# ProProject_AGV_VH723_MAIN_BOARD_2024-06-.net
KiCad netlist of a schematic drawn in EasyEDA Pro
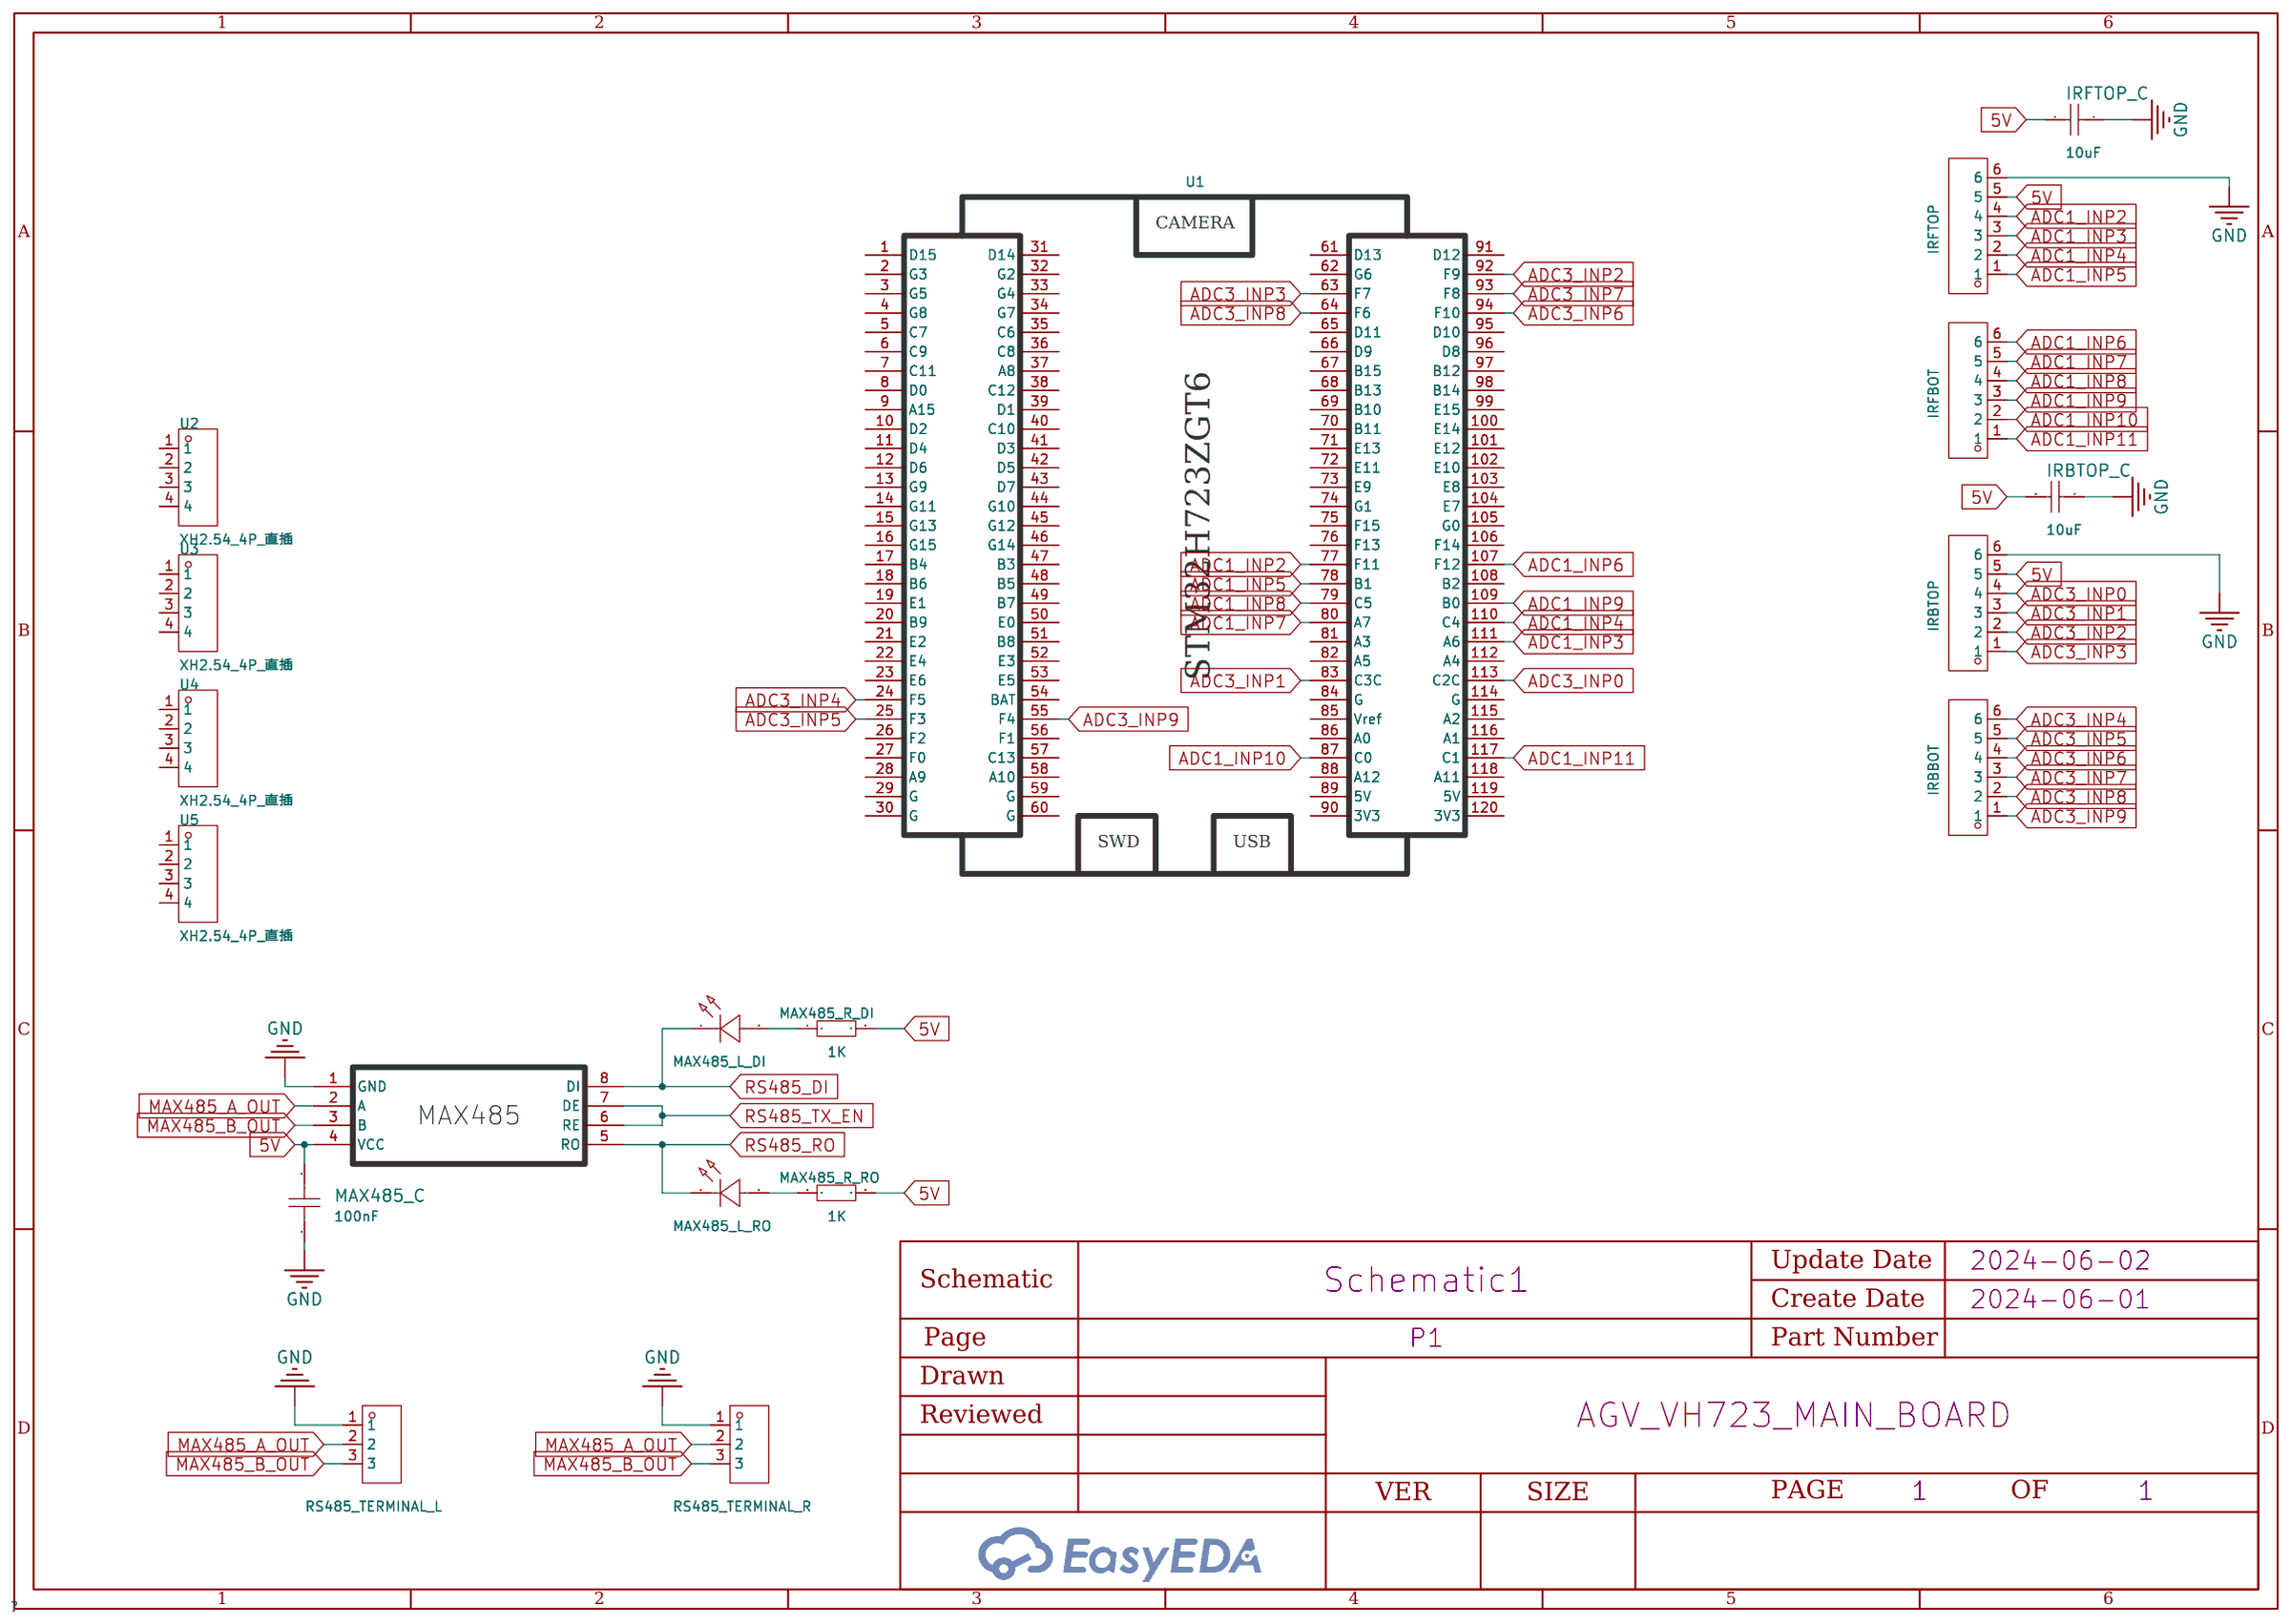
[diagram p0: schematic sheet]

(export (version "E")
  (design (tool "Eeschema 10.0.6"))
  (components
    (comp (ref "IRBBOT")
      (value "XH2.54*6P_直插")
      (footprint "easyedapro:CONN-TH_XH2.54-6P")
      (libsource (lib "easyedapro") (part "XH2.54*6P_直插"))
    )
    (comp (ref "IRBTOP")
      (value "XH2.54*6P_直插")
      (footprint "easyedapro:CONN-TH_XH2.54-6P")
      (libsource (lib "easyedapro") (part "XH2.54*6P_直插"))
    )
    (comp (ref "IRBTOP_C")
      (value "10uF")
      (footprint "easyedapro:C1206")
      (fields
        (field (name "Manufacturer Part") "CL31A106KOHNNNE")
        (field (name "Manufacturer") "SAMSUNG(三星)")
      )
      (libsource (lib "easyedapro") (part "CL31A106KOHNNNE"))
    )
    (comp (ref "IRFBOT")
      (value "XH2.54*6P_直插")
      (footprint "easyedapro:CONN-TH_XH2.54-6P")
      (libsource (lib "easyedapro") (part "XH2.54*6P_直插"))
    )
    (comp (ref "IRFTOP")
      (value "XH2.54*6P_直插")
      (footprint "easyedapro:CONN-TH_XH2.54-6P")
      (libsource (lib "easyedapro") (part "XH2.54*6P_直插"))
    )
    (comp (ref "IRFTOP_C")
      (value "10uF")
      (footprint "easyedapro:C1206")
      (fields
        (field (name "Manufacturer Part") "CL31A106KOHNNNE")
        (field (name "Manufacturer") "SAMSUNG(三星)")
      )
      (libsource (lib "easyedapro") (part "CL31A106KOHNNNE"))
    )
    (comp (ref "MAX485_C")
      (value "100nF")
      (footprint "easyedapro:C1206")
      (fields (field (name "Manufacturer Part") "1206B104K500CT") (field (name "Manufacturer") "Walsin(华新科)"))
      (libsource (lib "easyedapro") (part "1206B104K500"))
    )
    (comp (ref "MAX485_L_DI")
      (value "LED1206")
      (footprint "easyedapro:LED1206-RD")
      (libsource (lib "easyedapro") (part "LED1206"))
    )
    (comp (ref "MAX485_L_RO")
      (value "LED1206")
      (footprint "easyedapro:LED1206-RD")
      (libsource (lib "easyedapro") (part "LED1206"))
    )
    (comp (ref "MAX485_R_DI")
      (value "1K")
      (footprint "easyedapro:R0603")
      (libsource (lib "easyedapro") (part "Res"))
    )
    (comp (ref "MAX485_R_RO")
      (value "1K")
      (footprint "easyedapro:R0603")
      (libsource (lib "easyedapro") (part "Res"))
    )
    (comp (ref "RS485_TERMINAL_L")
      (value "MX128L-5.08-03P-GN01-Cu-Y-A")
      (footprint "easyedapro:CONN-TH_3P-P5.08_MX128L-5.08-03P-GN01-CU-Y-A")
      (fields (field (name "Manufacturer") "MAX(迈旭)"))
      (libsource (lib "easyedapro") (part "MX128L-5.08-03P-GN01-CU-Y-A"))
    )
    (comp (ref "RS485_TERMINAL_R")
      (value "MX128L-5.08-03P-GN01-Cu-Y-A")
      (footprint "easyedapro:CONN-TH_3P-P5.08_MX128L-5.08-03P-GN01-CU-Y-A")
      (fields (field (name "Manufacturer") "MAX(迈旭)"))
      (libsource (lib "easyedapro") (part "MX128L-5.08-03P-GN01-CU-Y-A"))
    )
    (comp (ref "U1")
      (value "STM32H723ZGT6")
      (footprint "easyedapro:STM32H723ZGT6 DEV BOARD FOOTPRINT")
      (description "STM32H723ZGT6 Core Board and Development Board model made by Araf Israk")
      (libsource (lib "easyedapro") (part "stm32h723zgt6 dev board"))
    )
    (comp (ref "U2")
      (value "XH2.54_4P_直插")
      (footprint "easyedapro:CONN-TH_4P-P2.50-XH2.54-4P")
      (libsource (lib "easyedapro") (part "XH2.54_4P_直插"))
    )
    (comp (ref "U3")
      (value "XH2.54_4P_直插")
      (footprint "easyedapro:CONN-TH_4P-P2.50-XH2.54-4P")
      (libsource (lib "easyedapro") (part "XH2.54_4P_直插"))
    )
    (comp (ref "U4")
      (value "XH2.54_4P_直插")
      (footprint "easyedapro:CONN-TH_4P-P2.50-XH2.54-4P")
      (libsource (lib "easyedapro") (part "XH2.54_4P_直插"))
    )
    (comp (ref "U5")
      (value "XH2.54_4P_直插")
      (footprint "easyedapro:CONN-TH_4P-P2.50-XH2.54-4P")
      (libsource (lib "easyedapro") (part "XH2.54_4P_直插"))
    )
    (comp (ref "U6")
      (value "MAX485 IC RS485 Module")
      (footprint "easyedapro:RS485-arafisrak")
      (description "MAX485 IC RS485 Module (modified)")
      (libsource (lib "easyedapro") (part "RS485 Module"))
    )
  )
  (nets
    (net (code "1") (name "5V") (class "Default")
      (node (ref "IRBTOP") (pin "5") (pinfunction "5_5") (pintype "unspecified"))
      (node (ref "IRBTOP_C") (pin "2") (pinfunction "2_2") (pintype "input"))
      (node (ref "IRFTOP") (pin "5") (pinfunction "5_5") (pintype "unspecified"))
      (node (ref "IRFTOP_C") (pin "2") (pinfunction "2_2") (pintype "input"))
      (node (ref "MAX485_C") (pin "2") (pinfunction "2_2") (pintype "input"))
      (node (ref "MAX485_R_DI") (pin "2") (pinfunction "2_2") (pintype "input"))
      (node (ref "MAX485_R_RO") (pin "2") (pinfunction "2_2") (pintype "input"))
      (node (ref "U6") (pin "4") (pinfunction "VCC_4") (pintype "input"))
    )
    (net (code "2") (name "ADC1_INP2") (class "Default")
      (node (ref "IRFTOP") (pin "4") (pinfunction "4_4") (pintype "unspecified"))
      (node (ref "U1") (pin "77") (pinfunction "F11_77") (pintype "input"))
    )
    (net (code "3") (name "ADC1_INP3") (class "Default")
      (node (ref "IRFTOP") (pin "3") (pinfunction "3_3") (pintype "unspecified"))
      (node (ref "U1") (pin "111") (pinfunction "A6_111") (pintype "input"))
    )
    (net (code "4") (name "ADC1_INP4") (class "Default")
      (node (ref "IRFTOP") (pin "2") (pinfunction "2_2") (pintype "unspecified"))
      (node (ref "U1") (pin "110") (pinfunction "C4_110") (pintype "input"))
    )
    (net (code "5") (name "ADC1_INP5") (class "Default")
      (node (ref "IRFTOP") (pin "1") (pinfunction "1_1") (pintype "unspecified"))
      (node (ref "U1") (pin "78") (pinfunction "B1_78") (pintype "input"))
    )
    (net (code "6") (name "ADC1_INP6") (class "Default")
      (node (ref "IRFBOT") (pin "6") (pinfunction "6_6") (pintype "unspecified"))
      (node (ref "U1") (pin "107") (pinfunction "F12_107") (pintype "input"))
    )
    (net (code "7") (name "ADC1_INP7") (class "Default")
      (node (ref "IRFBOT") (pin "5") (pinfunction "5_5") (pintype "unspecified"))
      (node (ref "U1") (pin "80") (pinfunction "A7_80") (pintype "input"))
    )
    (net (code "8") (name "ADC1_INP8") (class "Default")
      (node (ref "IRFBOT") (pin "4") (pinfunction "4_4") (pintype "unspecified"))
      (node (ref "U1") (pin "79") (pinfunction "C5_79") (pintype "input"))
    )
    (net (code "9") (name "ADC1_INP9") (class "Default")
      (node (ref "IRFBOT") (pin "3") (pinfunction "3_3") (pintype "unspecified"))
      (node (ref "U1") (pin "109") (pinfunction "B0_109") (pintype "input"))
    )
    (net (code "10") (name "ADC1_INP10") (class "Default")
      (node (ref "IRFBOT") (pin "2") (pinfunction "2_2") (pintype "unspecified"))
      (node (ref "U1") (pin "87") (pinfunction "C0_87") (pintype "input"))
    )
    (net (code "11") (name "ADC1_INP11") (class "Default")
      (node (ref "IRFBOT") (pin "1") (pinfunction "1_1") (pintype "unspecified"))
      (node (ref "U1") (pin "117") (pinfunction "C1_117") (pintype "input"))
    )
    (net (code "12") (name "ADC3_INP0") (class "Default")
      (node (ref "IRBTOP") (pin "4") (pinfunction "4_4") (pintype "unspecified"))
      (node (ref "U1") (pin "113") (pinfunction "C2C_113") (pintype "input"))
    )
    (net (code "13") (name "ADC3_INP1") (class "Default")
      (node (ref "IRBTOP") (pin "3") (pinfunction "3_3") (pintype "unspecified"))
      (node (ref "U1") (pin "83") (pinfunction "C3C_83") (pintype "input"))
    )
    (net (code "14") (name "ADC3_INP2") (class "Default")
      (node (ref "IRBTOP") (pin "2") (pinfunction "2_2") (pintype "unspecified"))
      (node (ref "U1") (pin "92") (pinfunction "F9_92") (pintype "input"))
    )
    (net (code "15") (name "ADC3_INP3") (class "Default")
      (node (ref "IRBTOP") (pin "1") (pinfunction "1_1") (pintype "unspecified"))
      (node (ref "U1") (pin "63") (pinfunction "F7_63") (pintype "input"))
    )
    (net (code "16") (name "ADC3_INP4") (class "Default")
      (node (ref "IRBBOT") (pin "6") (pinfunction "6_6") (pintype "unspecified"))
      (node (ref "U1") (pin "24") (pinfunction "F5_24") (pintype "input"))
    )
    (net (code "17") (name "ADC3_INP5") (class "Default")
      (node (ref "IRBBOT") (pin "5") (pinfunction "5_5") (pintype "unspecified"))
      (node (ref "U1") (pin "25") (pinfunction "F3_25") (pintype "input"))
    )
    (net (code "18") (name "ADC3_INP6") (class "Default")
      (node (ref "IRBBOT") (pin "4") (pinfunction "4_4") (pintype "unspecified"))
      (node (ref "U1") (pin "94") (pinfunction "F10_94") (pintype "input"))
    )
    (net (code "19") (name "ADC3_INP7") (class "Default")
      (node (ref "IRBBOT") (pin "3") (pinfunction "3_3") (pintype "unspecified"))
      (node (ref "U1") (pin "93") (pinfunction "F8_93") (pintype "input"))
    )
    (net (code "20") (name "ADC3_INP8") (class "Default")
      (node (ref "IRBBOT") (pin "2") (pinfunction "2_2") (pintype "unspecified"))
      (node (ref "U1") (pin "64") (pinfunction "F6_64") (pintype "input"))
    )
    (net (code "21") (name "ADC3_INP9") (class "Default")
      (node (ref "IRBBOT") (pin "1") (pinfunction "1_1") (pintype "unspecified"))
      (node (ref "U1") (pin "55") (pinfunction "F4_55") (pintype "input"))
    )
    (net (code "22") (name "GND") (class "Default")
      (node (ref "IRBTOP") (pin "6") (pinfunction "6_6") (pintype "unspecified"))
      (node (ref "IRBTOP_C") (pin "1") (pinfunction "1_1") (pintype "input"))
      (node (ref "IRFTOP") (pin "6") (pinfunction "6_6") (pintype "unspecified"))
      (node (ref "IRFTOP_C") (pin "1") (pinfunction "1_1") (pintype "input"))
      (node (ref "MAX485_C") (pin "1") (pinfunction "1_1") (pintype "input"))
      (node (ref "RS485_TERMINAL_L") (pin "1") (pinfunction "1_1") (pintype "unspecified"))
      (node (ref "RS485_TERMINAL_R") (pin "1") (pinfunction "1_1") (pintype "unspecified"))
      (node (ref "U6") (pin "1") (pinfunction "GND_1") (pintype "input"))
    )
    (net (code "23") (name "MAX485_A_OUT") (class "Default")
      (node (ref "RS485_TERMINAL_L") (pin "2") (pinfunction "2_2") (pintype "unspecified"))
      (node (ref "RS485_TERMINAL_R") (pin "2") (pinfunction "2_2") (pintype "unspecified"))
      (node (ref "U6") (pin "2") (pinfunction "A_2") (pintype "input"))
    )
    (net (code "24") (name "MAX485_B_OUT") (class "Default")
      (node (ref "RS485_TERMINAL_L") (pin "3") (pinfunction "3_3") (pintype "unspecified"))
      (node (ref "RS485_TERMINAL_R") (pin "3") (pinfunction "3_3") (pintype "unspecified"))
      (node (ref "U6") (pin "3") (pinfunction "B_3") (pintype "input"))
    )
    (net (code "25") (name "Net-(MAX485_L_DI-A)") (class "Default")
      (node (ref "MAX485_L_DI") (pin "2") (pinfunction "A_2") (pintype "input"))
      (node (ref "MAX485_R_DI") (pin "1") (pinfunction "1_1") (pintype "input"))
    )
    (net (code "26") (name "Net-(MAX485_L_RO-A)") (class "Default")
      (node (ref "MAX485_L_RO") (pin "2") (pinfunction "A_2") (pintype "input"))
      (node (ref "MAX485_R_RO") (pin "1") (pinfunction "1_1") (pintype "input"))
    )
    (net (code "27") (name "RS485_DI") (class "Default")
      (node (ref "MAX485_L_DI") (pin "1") (pinfunction "K_1") (pintype "input"))
      (node (ref "U6") (pin "8") (pinfunction "DI_8") (pintype "input"))
    )
    (net (code "28") (name "RS485_RO") (class "Default")
      (node (ref "MAX485_L_RO") (pin "1") (pinfunction "K_1") (pintype "input"))
      (node (ref "U6") (pin "5") (pinfunction "RO_5") (pintype "input"))
    )
    (net (code "29") (name "RS485_TX_EN") (class "Default")
      (node (ref "U6") (pin "6") (pinfunction "RE_6") (pintype "input"))
      (node (ref "U6") (pin "7") (pinfunction "DE_7") (pintype "input"))
    )
    (net (code "30") (name "unconnected-(U1-3V3-Pad90)") (class "Default")
      (node (ref "U1") (pin "90") (pinfunction "3V3_90") (pintype "input"))
    )
    (net (code "31") (name "unconnected-(U1-3V3-Pad120)") (class "Default")
      (node (ref "U1") (pin "120") (pinfunction "3V3_120") (pintype "input"))
    )
    (net (code "32") (name "unconnected-(U1-5V-Pad89)") (class "Default")
      (node (ref "U1") (pin "89") (pinfunction "5V_89") (pintype "input"))
    )
    (net (code "33") (name "unconnected-(U1-5V-Pad119)") (class "Default")
      (node (ref "U1") (pin "119") (pinfunction "5V_119") (pintype "input"))
    )
    (net (code "34") (name "unconnected-(U1-A0-Pad86)") (class "Default")
      (node (ref "U1") (pin "86") (pinfunction "A0_86") (pintype "input"))
    )
    (net (code "35") (name "unconnected-(U1-A1-Pad116)") (class "Default")
      (node (ref "U1") (pin "116") (pinfunction "A1_116") (pintype "input"))
    )
    (net (code "36") (name "unconnected-(U1-A2-Pad115)") (class "Default")
      (node (ref "U1") (pin "115") (pinfunction "A2_115") (pintype "input"))
    )
    (net (code "37") (name "unconnected-(U1-A3-Pad81)") (class "Default")
      (node (ref "U1") (pin "81") (pinfunction "A3_81") (pintype "input"))
    )
    (net (code "38") (name "unconnected-(U1-A4-Pad112)") (class "Default")
      (node (ref "U1") (pin "112") (pinfunction "A4_112") (pintype "input"))
    )
    (net (code "39") (name "unconnected-(U1-A5-Pad82)") (class "Default")
      (node (ref "U1") (pin "82") (pinfunction "A5_82") (pintype "input"))
    )
    (net (code "40") (name "unconnected-(U1-A8-Pad37)") (class "Default")
      (node (ref "U1") (pin "37") (pinfunction "A8_37") (pintype "input"))
    )
    (net (code "41") (name "unconnected-(U1-A9-Pad28)") (class "Default")
      (node (ref "U1") (pin "28") (pinfunction "A9_28") (pintype "input"))
    )
    (net (code "42") (name "unconnected-(U1-A10-Pad58)") (class "Default")
      (node (ref "U1") (pin "58") (pinfunction "A10_58") (pintype "input"))
    )
    (net (code "43") (name "unconnected-(U1-A11-Pad118)") (class "Default")
      (node (ref "U1") (pin "118") (pinfunction "A11_118") (pintype "input"))
    )
    (net (code "44") (name "unconnected-(U1-A12-Pad88)") (class "Default")
      (node (ref "U1") (pin "88") (pinfunction "A12_88") (pintype "input"))
    )
    (net (code "45") (name "unconnected-(U1-A15-Pad9)") (class "Default")
      (node (ref "U1") (pin "9") (pinfunction "A15_9") (pintype "input"))
    )
    (net (code "46") (name "unconnected-(U1-B2-Pad108)") (class "Default")
      (node (ref "U1") (pin "108") (pinfunction "B2_108") (pintype "input"))
    )
    (net (code "47") (name "unconnected-(U1-B3-Pad47)") (class "Default")
      (node (ref "U1") (pin "47") (pinfunction "B3_47") (pintype "input"))
    )
    (net (code "48") (name "unconnected-(U1-B4-Pad17)") (class "Default")
      (node (ref "U1") (pin "17") (pinfunction "B4_17") (pintype "input"))
    )
    (net (code "49") (name "unconnected-(U1-B5-Pad48)") (class "Default")
      (node (ref "U1") (pin "48") (pinfunction "B5_48") (pintype "input"))
    )
    (net (code "50") (name "unconnected-(U1-B6-Pad18)") (class "Default")
      (node (ref "U1") (pin "18") (pinfunction "B6_18") (pintype "input"))
    )
    (net (code "51") (name "unconnected-(U1-B7-Pad49)") (class "Default")
      (node (ref "U1") (pin "49") (pinfunction "B7_49") (pintype "input"))
    )
    (net (code "52") (name "unconnected-(U1-B8-Pad51)") (class "Default")
      (node (ref "U1") (pin "51") (pinfunction "B8_51") (pintype "input"))
    )
    (net (code "53") (name "unconnected-(U1-B9-Pad20)") (class "Default")
      (node (ref "U1") (pin "20") (pinfunction "B9_20") (pintype "input"))
    )
    (net (code "54") (name "unconnected-(U1-B10-Pad69)") (class "Default")
      (node (ref "U1") (pin "69") (pinfunction "B10_69") (pintype "input"))
    )
    (net (code "55") (name "unconnected-(U1-B11-Pad70)") (class "Default")
      (node (ref "U1") (pin "70") (pinfunction "B11_70") (pintype "input"))
    )
    (net (code "56") (name "unconnected-(U1-B12-Pad97)") (class "Default")
      (node (ref "U1") (pin "97") (pinfunction "B12_97") (pintype "input"))
    )
    (net (code "57") (name "unconnected-(U1-B13-Pad68)") (class "Default")
      (node (ref "U1") (pin "68") (pinfunction "B13_68") (pintype "input"))
    )
    (net (code "58") (name "unconnected-(U1-B14-Pad98)") (class "Default")
      (node (ref "U1") (pin "98") (pinfunction "B14_98") (pintype "input"))
    )
    (net (code "59") (name "unconnected-(U1-B15-Pad67)") (class "Default")
      (node (ref "U1") (pin "67") (pinfunction "B15_67") (pintype "input"))
    )
    (net (code "60") (name "unconnected-(U1-BAT-Pad54)") (class "Default")
      (node (ref "U1") (pin "54") (pinfunction "BAT_54") (pintype "input"))
    )
    (net (code "61") (name "unconnected-(U1-C6-Pad35)") (class "Default")
      (node (ref "U1") (pin "35") (pinfunction "C6_35") (pintype "input"))
    )
    (net (code "62") (name "unconnected-(U1-C7-Pad5)") (class "Default")
      (node (ref "U1") (pin "5") (pinfunction "C7_5") (pintype "input"))
    )
    (net (code "63") (name "unconnected-(U1-C8-Pad36)") (class "Default")
      (node (ref "U1") (pin "36") (pinfunction "C8_36") (pintype "input"))
    )
    (net (code "64") (name "unconnected-(U1-C9-Pad6)") (class "Default")
      (node (ref "U1") (pin "6") (pinfunction "C9_6") (pintype "input"))
    )
    (net (code "65") (name "unconnected-(U1-C10-Pad40)") (class "Default")
      (node (ref "U1") (pin "40") (pinfunction "C10_40") (pintype "input"))
    )
    (net (code "66") (name "unconnected-(U1-C11-Pad7)") (class "Default")
      (node (ref "U1") (pin "7") (pinfunction "C11_7") (pintype "input"))
    )
    (net (code "67") (name "unconnected-(U1-C12-Pad38)") (class "Default")
      (node (ref "U1") (pin "38") (pinfunction "C12_38") (pintype "input"))
    )
    (net (code "68") (name "unconnected-(U1-C13-Pad57)") (class "Default")
      (node (ref "U1") (pin "57") (pinfunction "C13_57") (pintype "input"))
    )
    (net (code "69") (name "unconnected-(U1-D0-Pad8)") (class "Default")
      (node (ref "U1") (pin "8") (pinfunction "D0_8") (pintype "input"))
    )
    (net (code "70") (name "unconnected-(U1-D1-Pad39)") (class "Default")
      (node (ref "U1") (pin "39") (pinfunction "D1_39") (pintype "input"))
    )
    (net (code "71") (name "unconnected-(U1-D2-Pad10)") (class "Default")
      (node (ref "U1") (pin "10") (pinfunction "D2_10") (pintype "input"))
    )
    (net (code "72") (name "unconnected-(U1-D3-Pad41)") (class "Default")
      (node (ref "U1") (pin "41") (pinfunction "D3_41") (pintype "input"))
    )
    (net (code "73") (name "unconnected-(U1-D4-Pad11)") (class "Default")
      (node (ref "U1") (pin "11") (pinfunction "D4_11") (pintype "input"))
    )
    (net (code "74") (name "unconnected-(U1-D5-Pad42)") (class "Default")
      (node (ref "U1") (pin "42") (pinfunction "D5_42") (pintype "input"))
    )
    (net (code "75") (name "unconnected-(U1-D6-Pad12)") (class "Default")
      (node (ref "U1") (pin "12") (pinfunction "D6_12") (pintype "input"))
    )
    (net (code "76") (name "unconnected-(U1-D7-Pad43)") (class "Default")
      (node (ref "U1") (pin "43") (pinfunction "D7_43") (pintype "input"))
    )
    (net (code "77") (name "unconnected-(U1-D8-Pad96)") (class "Default")
      (node (ref "U1") (pin "96") (pinfunction "D8_96") (pintype "input"))
    )
    (net (code "78") (name "unconnected-(U1-D9-Pad66)") (class "Default")
      (node (ref "U1") (pin "66") (pinfunction "D9_66") (pintype "input"))
    )
    (net (code "79") (name "unconnected-(U1-D10-Pad95)") (class "Default")
      (node (ref "U1") (pin "95") (pinfunction "D10_95") (pintype "input"))
    )
    (net (code "80") (name "unconnected-(U1-D11-Pad65)") (class "Default")
      (node (ref "U1") (pin "65") (pinfunction "D11_65") (pintype "input"))
    )
    (net (code "81") (name "unconnected-(U1-D12-Pad91)") (class "Default")
      (node (ref "U1") (pin "91") (pinfunction "D12_91") (pintype "input"))
    )
    (net (code "82") (name "unconnected-(U1-D13-Pad61)") (class "Default")
      (node (ref "U1") (pin "61") (pinfunction "D13_61") (pintype "input"))
    )
    (net (code "83") (name "unconnected-(U1-D14-Pad31)") (class "Default")
      (node (ref "U1") (pin "31") (pinfunction "D14_31") (pintype "input"))
    )
    (net (code "84") (name "unconnected-(U1-D15-Pad1)") (class "Default")
      (node (ref "U1") (pin "1") (pinfunction "D15_1") (pintype "input"))
    )
    (net (code "85") (name "unconnected-(U1-E0-Pad50)") (class "Default")
      (node (ref "U1") (pin "50") (pinfunction "E0_50") (pintype "input"))
    )
    (net (code "86") (name "unconnected-(U1-E1-Pad19)") (class "Default")
      (node (ref "U1") (pin "19") (pinfunction "E1_19") (pintype "input"))
    )
    (net (code "87") (name "unconnected-(U1-E2-Pad21)") (class "Default")
      (node (ref "U1") (pin "21") (pinfunction "E2_21") (pintype "input"))
    )
    (net (code "88") (name "unconnected-(U1-E3-Pad52)") (class "Default")
      (node (ref "U1") (pin "52") (pinfunction "E3_52") (pintype "input"))
    )
    (net (code "89") (name "unconnected-(U1-E4-Pad22)") (class "Default")
      (node (ref "U1") (pin "22") (pinfunction "E4_22") (pintype "input"))
    )
    (net (code "90") (name "unconnected-(U1-E5-Pad53)") (class "Default")
      (node (ref "U1") (pin "53") (pinfunction "E5_53") (pintype "input"))
    )
    (net (code "91") (name "unconnected-(U1-E6-Pad23)") (class "Default")
      (node (ref "U1") (pin "23") (pinfunction "E6_23") (pintype "input"))
    )
    (net (code "92") (name "unconnected-(U1-E7-Pad104)") (class "Default")
      (node (ref "U1") (pin "104") (pinfunction "E7_104") (pintype "input"))
    )
    (net (code "93") (name "unconnected-(U1-E8-Pad103)") (class "Default")
      (node (ref "U1") (pin "103") (pinfunction "E8_103") (pintype "input"))
    )
    (net (code "94") (name "unconnected-(U1-E9-Pad73)") (class "Default")
      (node (ref "U1") (pin "73") (pinfunction "E9_73") (pintype "input"))
    )
    (net (code "95") (name "unconnected-(U1-E10-Pad102)") (class "Default")
      (node (ref "U1") (pin "102") (pinfunction "E10_102") (pintype "input"))
    )
    (net (code "96") (name "unconnected-(U1-E11-Pad72)") (class "Default")
      (node (ref "U1") (pin "72") (pinfunction "E11_72") (pintype "input"))
    )
    (net (code "97") (name "unconnected-(U1-E12-Pad101)") (class "Default")
      (node (ref "U1") (pin "101") (pinfunction "E12_101") (pintype "input"))
    )
    (net (code "98") (name "unconnected-(U1-E13-Pad71)") (class "Default")
      (node (ref "U1") (pin "71") (pinfunction "E13_71") (pintype "input"))
    )
    (net (code "99") (name "unconnected-(U1-E14-Pad100)") (class "Default")
      (node (ref "U1") (pin "100") (pinfunction "E14_100") (pintype "input"))
    )
    (net (code "100") (name "unconnected-(U1-E15-Pad99)") (class "Default")
      (node (ref "U1") (pin "99") (pinfunction "E15_99") (pintype "input"))
    )
    (net (code "101") (name "unconnected-(U1-F0-Pad27)") (class "Default")
      (node (ref "U1") (pin "27") (pinfunction "F0_27") (pintype "input"))
    )
    (net (code "102") (name "unconnected-(U1-F1-Pad56)") (class "Default")
      (node (ref "U1") (pin "56") (pinfunction "F1_56") (pintype "input"))
    )
    (net (code "103") (name "unconnected-(U1-F2-Pad26)") (class "Default")
      (node (ref "U1") (pin "26") (pinfunction "F2_26") (pintype "input"))
    )
    (net (code "104") (name "unconnected-(U1-F13-Pad76)") (class "Default")
      (node (ref "U1") (pin "76") (pinfunction "F13_76") (pintype "input"))
    )
    (net (code "105") (name "unconnected-(U1-F14-Pad106)") (class "Default")
      (node (ref "U1") (pin "106") (pinfunction "F14_106") (pintype "input"))
    )
    (net (code "106") (name "unconnected-(U1-F15-Pad75)") (class "Default")
      (node (ref "U1") (pin "75") (pinfunction "F15_75") (pintype "input"))
    )
    (net (code "107") (name "unconnected-(U1-G-Pad29)") (class "Default")
      (node (ref "U1") (pin "29") (pinfunction "G_29") (pintype "input"))
    )
    (net (code "108") (name "unconnected-(U1-G-Pad30)") (class "Default")
      (node (ref "U1") (pin "30") (pinfunction "G_30") (pintype "input"))
    )
    (net (code "109") (name "unconnected-(U1-G-Pad59)") (class "Default")
      (node (ref "U1") (pin "59") (pinfunction "G_59") (pintype "input"))
    )
    (net (code "110") (name "unconnected-(U1-G-Pad60)") (class "Default")
      (node (ref "U1") (pin "60") (pinfunction "G_60") (pintype "input"))
    )
    (net (code "111") (name "unconnected-(U1-G-Pad84)") (class "Default")
      (node (ref "U1") (pin "84") (pinfunction "G_84") (pintype "input"))
    )
    (net (code "112") (name "unconnected-(U1-G-Pad114)") (class "Default")
      (node (ref "U1") (pin "114") (pinfunction "G_114") (pintype "input"))
    )
    (net (code "113") (name "unconnected-(U1-G0-Pad105)") (class "Default")
      (node (ref "U1") (pin "105") (pinfunction "G0_105") (pintype "input"))
    )
    (net (code "114") (name "unconnected-(U1-G1-Pad74)") (class "Default")
      (node (ref "U1") (pin "74") (pinfunction "G1_74") (pintype "input"))
    )
    (net (code "115") (name "unconnected-(U1-G2-Pad32)") (class "Default")
      (node (ref "U1") (pin "32") (pinfunction "G2_32") (pintype "input"))
    )
    (net (code "116") (name "unconnected-(U1-G3-Pad2)") (class "Default")
      (node (ref "U1") (pin "2") (pinfunction "G3_2") (pintype "input"))
    )
    (net (code "117") (name "unconnected-(U1-G4-Pad33)") (class "Default")
      (node (ref "U1") (pin "33") (pinfunction "G4_33") (pintype "input"))
    )
    (net (code "118") (name "unconnected-(U1-G5-Pad3)") (class "Default")
      (node (ref "U1") (pin "3") (pinfunction "G5_3") (pintype "input"))
    )
    (net (code "119") (name "unconnected-(U1-G6-Pad62)") (class "Default")
      (node (ref "U1") (pin "62") (pinfunction "G6_62") (pintype "input"))
    )
    (net (code "120") (name "unconnected-(U1-G7-Pad34)") (class "Default")
      (node (ref "U1") (pin "34") (pinfunction "G7_34") (pintype "input"))
    )
    (net (code "121") (name "unconnected-(U1-G8-Pad4)") (class "Default")
      (node (ref "U1") (pin "4") (pinfunction "G8_4") (pintype "input"))
    )
    (net (code "122") (name "unconnected-(U1-G9-Pad13)") (class "Default")
      (node (ref "U1") (pin "13") (pinfunction "G9_13") (pintype "input"))
    )
    (net (code "123") (name "unconnected-(U1-G10-Pad44)") (class "Default")
      (node (ref "U1") (pin "44") (pinfunction "G10_44") (pintype "input"))
    )
    (net (code "124") (name "unconnected-(U1-G11-Pad14)") (class "Default")
      (node (ref "U1") (pin "14") (pinfunction "G11_14") (pintype "input"))
    )
    (net (code "125") (name "unconnected-(U1-G12-Pad45)") (class "Default")
      (node (ref "U1") (pin "45") (pinfunction "G12_45") (pintype "input"))
    )
    (net (code "126") (name "unconnected-(U1-G13-Pad15)") (class "Default")
      (node (ref "U1") (pin "15") (pinfunction "G13_15") (pintype "input"))
    )
    (net (code "127") (name "unconnected-(U1-G14-Pad46)") (class "Default")
      (node (ref "U1") (pin "46") (pinfunction "G14_46") (pintype "input"))
    )
    (net (code "128") (name "unconnected-(U1-G15-Pad16)") (class "Default")
      (node (ref "U1") (pin "16") (pinfunction "G15_16") (pintype "input"))
    )
    (net (code "129") (name "unconnected-(U1-Vref-Pad85)") (class "Default")
      (node (ref "U1") (pin "85") (pinfunction "Vref_85") (pintype "input"))
    )
    (net (code "130") (name "unconnected-(U2-Pad1)") (class "Default")
      (node (ref "U2") (pin "1") (pinfunction "1_1") (pintype "unspecified"))
    )
    (net (code "131") (name "unconnected-(U2-Pad2)") (class "Default")
      (node (ref "U2") (pin "2") (pinfunction "2_2") (pintype "unspecified"))
    )
    (net (code "132") (name "unconnected-(U2-Pad3)") (class "Default")
      (node (ref "U2") (pin "3") (pinfunction "3_3") (pintype "unspecified"))
    )
    (net (code "133") (name "unconnected-(U2-Pad4)") (class "Default")
      (node (ref "U2") (pin "4") (pinfunction "4_4") (pintype "unspecified"))
    )
    (net (code "134") (name "unconnected-(U3-Pad1)") (class "Default")
      (node (ref "U3") (pin "1") (pinfunction "1_1") (pintype "unspecified"))
    )
    (net (code "135") (name "unconnected-(U3-Pad2)") (class "Default")
      (node (ref "U3") (pin "2") (pinfunction "2_2") (pintype "unspecified"))
    )
    (net (code "136") (name "unconnected-(U3-Pad3)") (class "Default")
      (node (ref "U3") (pin "3") (pinfunction "3_3") (pintype "unspecified"))
    )
    (net (code "137") (name "unconnected-(U3-Pad4)") (class "Default")
      (node (ref "U3") (pin "4") (pinfunction "4_4") (pintype "unspecified"))
    )
    (net (code "138") (name "unconnected-(U4-Pad1)") (class "Default")
      (node (ref "U4") (pin "1") (pinfunction "1_1") (pintype "unspecified"))
    )
    (net (code "139") (name "unconnected-(U4-Pad2)") (class "Default")
      (node (ref "U4") (pin "2") (pinfunction "2_2") (pintype "unspecified"))
    )
    (net (code "140") (name "unconnected-(U4-Pad3)") (class "Default")
      (node (ref "U4") (pin "3") (pinfunction "3_3") (pintype "unspecified"))
    )
    (net (code "141") (name "unconnected-(U4-Pad4)") (class "Default")
      (node (ref "U4") (pin "4") (pinfunction "4_4") (pintype "unspecified"))
    )
    (net (code "142") (name "unconnected-(U5-Pad1)") (class "Default")
      (node (ref "U5") (pin "1") (pinfunction "1_1") (pintype "unspecified"))
    )
    (net (code "143") (name "unconnected-(U5-Pad2)") (class "Default")
      (node (ref "U5") (pin "2") (pinfunction "2_2") (pintype "unspecified"))
    )
    (net (code "144") (name "unconnected-(U5-Pad3)") (class "Default")
      (node (ref "U5") (pin "3") (pinfunction "3_3") (pintype "unspecified"))
    )
    (net (code "145") (name "unconnected-(U5-Pad4)") (class "Default")
      (node (ref "U5") (pin "4") (pinfunction "4_4") (pintype "unspecified"))
    )
  )
)
